# Sheet2.net
KiCad netlist of a schematic drawn in Altium Designer
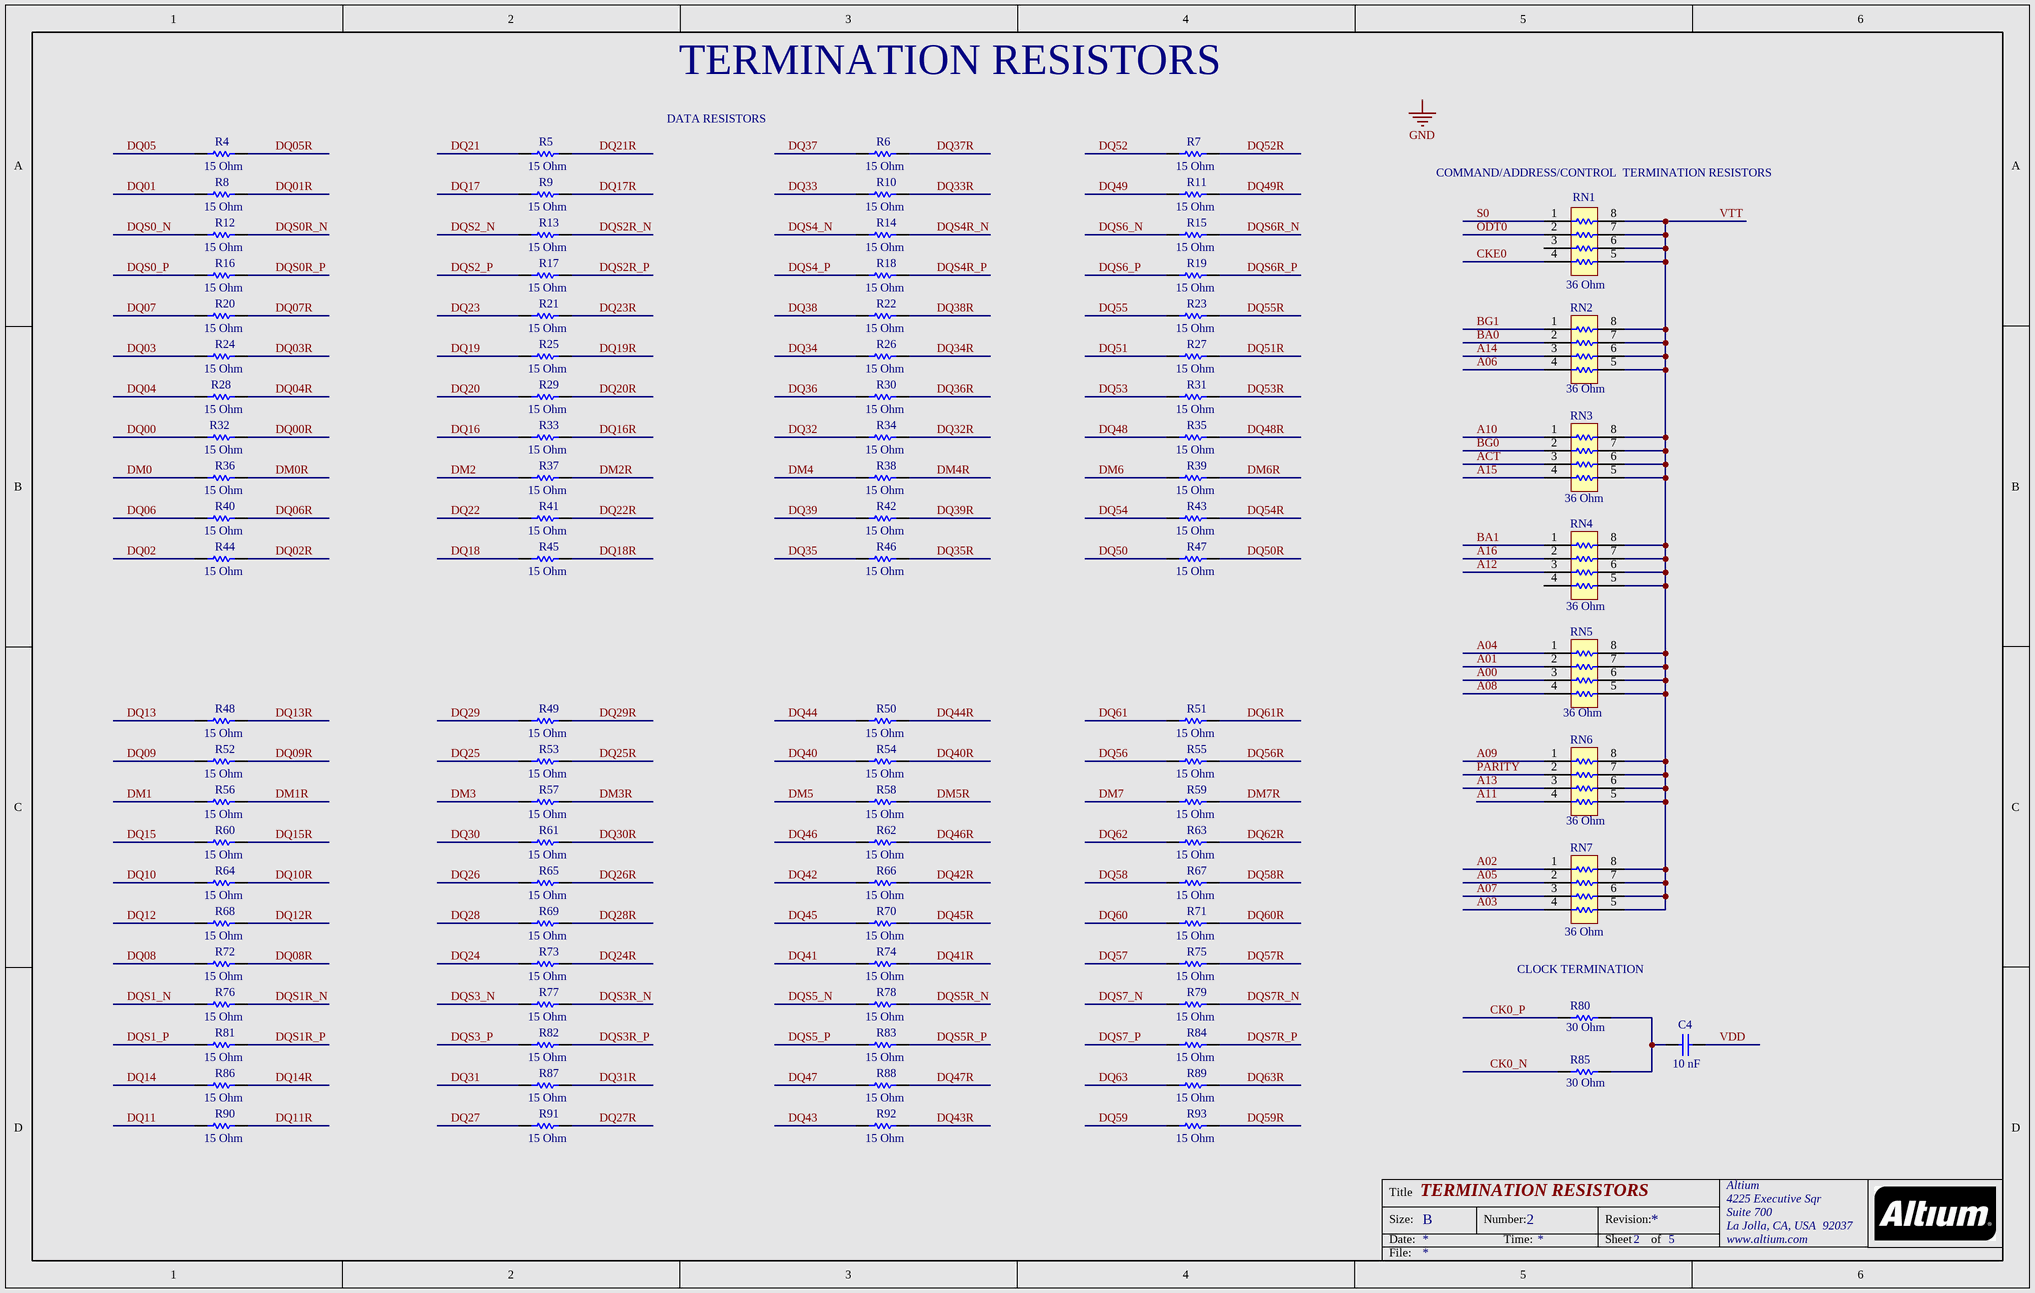
[diagram p0: Sheet2.SchDoc]

(export (version "E")
  (design (tool "Eeschema 10.0.6"))
  (components
    (comp (ref "C4")
      (value "C1005X7R1E103M050BB")
      (footprint "CAPC1005X55X10NL05")
      (description "Chip Capacitor, 10 nF, +/- 15%, 25 V, -55 to 125 degC, 0402 (1005 Metric), RoHS, Tape and Reel")
      (fields (field (name "TOLERANCE") "20%") (field (name "CAPACITANCE") "10 nF"))
      (libsource (lib "Altium Content Vault") (part "CMP-1663-00012-1"))
    )
    (comp (ref "R4")
      (value "ERJ-1GEJ150C")
      (footprint "RESC0603X26X15ML03T05")
      (description "Chip Resistor, 15 Ohm, +/- 5%, 0.05 W, -55 to 125 degC, 0201 (0603 Metric), RoHS, Tape and Reel")
      (fields (field (name "RESISTANCE") "15 Ohm") (field (name "TOLERANCE") "5%"))
      (libsource (lib "Altium Content Vault") (part "CMP-2004-03155-3"))
    )
    (comp (ref "R5")
      (value "ERJ-1GEJ150C")
      (footprint "RESC0603X26X15ML03T05")
      (description "Chip Resistor, 15 Ohm, +/- 5%, 0.05 W, -55 to 125 degC, 0201 (0603 Metric), RoHS, Tape and Reel")
      (fields (field (name "RESISTANCE") "15 Ohm") (field (name "TOLERANCE") "5%"))
      (libsource (lib "Altium Content Vault") (part "CMP-2004-03155-3"))
    )
    (comp (ref "R6")
      (value "ERJ-1GEJ150C")
      (footprint "RESC0603X26X15ML03T05")
      (description "Chip Resistor, 15 Ohm, +/- 5%, 0.05 W, -55 to 125 degC, 0201 (0603 Metric), RoHS, Tape and Reel")
      (fields (field (name "RESISTANCE") "15 Ohm") (field (name "TOLERANCE") "5%"))
      (libsource (lib "Altium Content Vault") (part "CMP-2004-03155-3"))
    )
    (comp (ref "R7")
      (value "ERJ-1GEJ150C")
      (footprint "RESC0603X26X15ML03T05")
      (description "Chip Resistor, 15 Ohm, +/- 5%, 0.05 W, -55 to 125 degC, 0201 (0603 Metric), RoHS, Tape and Reel")
      (fields (field (name "RESISTANCE") "15 Ohm") (field (name "TOLERANCE") "5%"))
      (libsource (lib "Altium Content Vault") (part "CMP-2004-03155-3"))
    )
    (comp (ref "R8")
      (value "ERJ-1GEJ150C")
      (footprint "RESC0603X26X15ML03T05")
      (description "Chip Resistor, 15 Ohm, +/- 5%, 0.05 W, -55 to 125 degC, 0201 (0603 Metric), RoHS, Tape and Reel")
      (fields (field (name "RESISTANCE") "15 Ohm") (field (name "TOLERANCE") "5%"))
      (libsource (lib "Altium Content Vault") (part "CMP-2004-03155-3"))
    )
    (comp (ref "R9")
      (value "ERJ-1GEJ150C")
      (footprint "RESC0603X26X15ML03T05")
      (description "Chip Resistor, 15 Ohm, +/- 5%, 0.05 W, -55 to 125 degC, 0201 (0603 Metric), RoHS, Tape and Reel")
      (fields (field (name "RESISTANCE") "15 Ohm") (field (name "TOLERANCE") "5%"))
      (libsource (lib "Altium Content Vault") (part "CMP-2004-03155-3"))
    )
    (comp (ref "R10")
      (value "ERJ-1GEJ150C")
      (footprint "RESC0603X26X15ML03T05")
      (description "Chip Resistor, 15 Ohm, +/- 5%, 0.05 W, -55 to 125 degC, 0201 (0603 Metric), RoHS, Tape and Reel")
      (fields (field (name "RESISTANCE") "15 Ohm") (field (name "TOLERANCE") "5%"))
      (libsource (lib "Altium Content Vault") (part "CMP-2004-03155-3"))
    )
    (comp (ref "R11")
      (value "ERJ-1GEJ150C")
      (footprint "RESC0603X26X15ML03T05")
      (description "Chip Resistor, 15 Ohm, +/- 5%, 0.05 W, -55 to 125 degC, 0201 (0603 Metric), RoHS, Tape and Reel")
      (fields (field (name "RESISTANCE") "15 Ohm") (field (name "TOLERANCE") "5%"))
      (libsource (lib "Altium Content Vault") (part "CMP-2004-03155-3"))
    )
    (comp (ref "R12")
      (value "ERJ-1GEJ150C")
      (footprint "RESC0603X26X15ML03T05")
      (description "Chip Resistor, 15 Ohm, +/- 5%, 0.05 W, -55 to 125 degC, 0201 (0603 Metric), RoHS, Tape and Reel")
      (fields (field (name "RESISTANCE") "15 Ohm") (field (name "TOLERANCE") "5%"))
      (libsource (lib "Altium Content Vault") (part "CMP-2004-03155-3"))
    )
    (comp (ref "R13")
      (value "ERJ-1GEJ150C")
      (footprint "RESC0603X26X15ML03T05")
      (description "Chip Resistor, 15 Ohm, +/- 5%, 0.05 W, -55 to 125 degC, 0201 (0603 Metric), RoHS, Tape and Reel")
      (fields (field (name "RESISTANCE") "15 Ohm") (field (name "TOLERANCE") "5%"))
      (libsource (lib "Altium Content Vault") (part "CMP-2004-03155-3"))
    )
    (comp (ref "R14")
      (value "ERJ-1GEJ150C")
      (footprint "RESC0603X26X15ML03T05")
      (description "Chip Resistor, 15 Ohm, +/- 5%, 0.05 W, -55 to 125 degC, 0201 (0603 Metric), RoHS, Tape and Reel")
      (fields (field (name "RESISTANCE") "15 Ohm") (field (name "TOLERANCE") "5%"))
      (libsource (lib "Altium Content Vault") (part "CMP-2004-03155-3"))
    )
    (comp (ref "R15")
      (value "ERJ-1GEJ150C")
      (footprint "RESC0603X26X15ML03T05")
      (description "Chip Resistor, 15 Ohm, +/- 5%, 0.05 W, -55 to 125 degC, 0201 (0603 Metric), RoHS, Tape and Reel")
      (fields (field (name "RESISTANCE") "15 Ohm") (field (name "TOLERANCE") "5%"))
      (libsource (lib "Altium Content Vault") (part "CMP-2004-03155-3"))
    )
    (comp (ref "R16")
      (value "ERJ-1GEJ150C")
      (footprint "RESC0603X26X15ML03T05")
      (description "Chip Resistor, 15 Ohm, +/- 5%, 0.05 W, -55 to 125 degC, 0201 (0603 Metric), RoHS, Tape and Reel")
      (fields (field (name "RESISTANCE") "15 Ohm") (field (name "TOLERANCE") "5%"))
      (libsource (lib "Altium Content Vault") (part "CMP-2004-03155-3"))
    )
    (comp (ref "R17")
      (value "ERJ-1GEJ150C")
      (footprint "RESC0603X26X15ML03T05")
      (description "Chip Resistor, 15 Ohm, +/- 5%, 0.05 W, -55 to 125 degC, 0201 (0603 Metric), RoHS, Tape and Reel")
      (fields (field (name "RESISTANCE") "15 Ohm") (field (name "TOLERANCE") "5%"))
      (libsource (lib "Altium Content Vault") (part "CMP-2004-03155-3"))
    )
    (comp (ref "R18")
      (value "ERJ-1GEJ150C")
      (footprint "RESC0603X26X15ML03T05")
      (description "Chip Resistor, 15 Ohm, +/- 5%, 0.05 W, -55 to 125 degC, 0201 (0603 Metric), RoHS, Tape and Reel")
      (fields (field (name "RESISTANCE") "15 Ohm") (field (name "TOLERANCE") "5%"))
      (libsource (lib "Altium Content Vault") (part "CMP-2004-03155-3"))
    )
    (comp (ref "R19")
      (value "ERJ-1GEJ150C")
      (footprint "RESC0603X26X15ML03T05")
      (description "Chip Resistor, 15 Ohm, +/- 5%, 0.05 W, -55 to 125 degC, 0201 (0603 Metric), RoHS, Tape and Reel")
      (fields (field (name "RESISTANCE") "15 Ohm") (field (name "TOLERANCE") "5%"))
      (libsource (lib "Altium Content Vault") (part "CMP-2004-03155-3"))
    )
    (comp (ref "R20")
      (value "ERJ-1GEJ150C")
      (footprint "RESC0603X26X15ML03T05")
      (description "Chip Resistor, 15 Ohm, +/- 5%, 0.05 W, -55 to 125 degC, 0201 (0603 Metric), RoHS, Tape and Reel")
      (fields (field (name "RESISTANCE") "15 Ohm") (field (name "TOLERANCE") "5%"))
      (libsource (lib "Altium Content Vault") (part "CMP-2004-03155-3"))
    )
    (comp (ref "R21")
      (value "ERJ-1GEJ150C")
      (footprint "RESC0603X26X15ML03T05")
      (description "Chip Resistor, 15 Ohm, +/- 5%, 0.05 W, -55 to 125 degC, 0201 (0603 Metric), RoHS, Tape and Reel")
      (fields (field (name "RESISTANCE") "15 Ohm") (field (name "TOLERANCE") "5%"))
      (libsource (lib "Altium Content Vault") (part "CMP-2004-03155-3"))
    )
    (comp (ref "R22")
      (value "ERJ-1GEJ150C")
      (footprint "RESC0603X26X15ML03T05")
      (description "Chip Resistor, 15 Ohm, +/- 5%, 0.05 W, -55 to 125 degC, 0201 (0603 Metric), RoHS, Tape and Reel")
      (fields (field (name "RESISTANCE") "15 Ohm") (field (name "TOLERANCE") "5%"))
      (libsource (lib "Altium Content Vault") (part "CMP-2004-03155-3"))
    )
    (comp (ref "R23")
      (value "ERJ-1GEJ150C")
      (footprint "RESC0603X26X15ML03T05")
      (description "Chip Resistor, 15 Ohm, +/- 5%, 0.05 W, -55 to 125 degC, 0201 (0603 Metric), RoHS, Tape and Reel")
      (fields (field (name "RESISTANCE") "15 Ohm") (field (name "TOLERANCE") "5%"))
      (libsource (lib "Altium Content Vault") (part "CMP-2004-03155-3"))
    )
    (comp (ref "R24")
      (value "ERJ-1GEJ150C")
      (footprint "RESC0603X26X15ML03T05")
      (description "Chip Resistor, 15 Ohm, +/- 5%, 0.05 W, -55 to 125 degC, 0201 (0603 Metric), RoHS, Tape and Reel")
      (fields (field (name "RESISTANCE") "15 Ohm") (field (name "TOLERANCE") "5%"))
      (libsource (lib "Altium Content Vault") (part "CMP-2004-03155-3"))
    )
    (comp (ref "R25")
      (value "ERJ-1GEJ150C")
      (footprint "RESC0603X26X15ML03T05")
      (description "Chip Resistor, 15 Ohm, +/- 5%, 0.05 W, -55 to 125 degC, 0201 (0603 Metric), RoHS, Tape and Reel")
      (fields (field (name "RESISTANCE") "15 Ohm") (field (name "TOLERANCE") "5%"))
      (libsource (lib "Altium Content Vault") (part "CMP-2004-03155-3"))
    )
    (comp (ref "R26")
      (value "ERJ-1GEJ150C")
      (footprint "RESC0603X26X15ML03T05")
      (description "Chip Resistor, 15 Ohm, +/- 5%, 0.05 W, -55 to 125 degC, 0201 (0603 Metric), RoHS, Tape and Reel")
      (fields (field (name "RESISTANCE") "15 Ohm") (field (name "TOLERANCE") "5%"))
      (libsource (lib "Altium Content Vault") (part "CMP-2004-03155-3"))
    )
    (comp (ref "R27")
      (value "ERJ-1GEJ150C")
      (footprint "RESC0603X26X15ML03T05")
      (description "Chip Resistor, 15 Ohm, +/- 5%, 0.05 W, -55 to 125 degC, 0201 (0603 Metric), RoHS, Tape and Reel")
      (fields (field (name "RESISTANCE") "15 Ohm") (field (name "TOLERANCE") "5%"))
      (libsource (lib "Altium Content Vault") (part "CMP-2004-03155-3"))
    )
    (comp (ref "R28")
      (value "ERJ-1GEJ150C")
      (footprint "RESC0603X26X15ML03T05")
      (description "Chip Resistor, 15 Ohm, +/- 5%, 0.05 W, -55 to 125 degC, 0201 (0603 Metric), RoHS, Tape and Reel")
      (fields (field (name "RESISTANCE") "15 Ohm") (field (name "TOLERANCE") "5%"))
      (libsource (lib "Altium Content Vault") (part "CMP-2004-03155-3"))
    )
    (comp (ref "R29")
      (value "ERJ-1GEJ150C")
      (footprint "RESC0603X26X15ML03T05")
      (description "Chip Resistor, 15 Ohm, +/- 5%, 0.05 W, -55 to 125 degC, 0201 (0603 Metric), RoHS, Tape and Reel")
      (fields (field (name "RESISTANCE") "15 Ohm") (field (name "TOLERANCE") "5%"))
      (libsource (lib "Altium Content Vault") (part "CMP-2004-03155-3"))
    )
    (comp (ref "R30")
      (value "ERJ-1GEJ150C")
      (footprint "RESC0603X26X15ML03T05")
      (description "Chip Resistor, 15 Ohm, +/- 5%, 0.05 W, -55 to 125 degC, 0201 (0603 Metric), RoHS, Tape and Reel")
      (fields (field (name "RESISTANCE") "15 Ohm") (field (name "TOLERANCE") "5%"))
      (libsource (lib "Altium Content Vault") (part "CMP-2004-03155-3"))
    )
    (comp (ref "R31")
      (value "ERJ-1GEJ150C")
      (footprint "RESC0603X26X15ML03T05")
      (description "Chip Resistor, 15 Ohm, +/- 5%, 0.05 W, -55 to 125 degC, 0201 (0603 Metric), RoHS, Tape and Reel")
      (fields (field (name "RESISTANCE") "15 Ohm") (field (name "TOLERANCE") "5%"))
      (libsource (lib "Altium Content Vault") (part "CMP-2004-03155-3"))
    )
    (comp (ref "R32")
      (value "ERJ-1GEJ150C")
      (footprint "RESC0603X26X15ML03T05")
      (description "Chip Resistor, 15 Ohm, +/- 5%, 0.05 W, -55 to 125 degC, 0201 (0603 Metric), RoHS, Tape and Reel")
      (fields (field (name "RESISTANCE") "15 Ohm") (field (name "TOLERANCE") "5%"))
      (libsource (lib "Altium Content Vault") (part "CMP-2004-03155-3"))
    )
    (comp (ref "R33")
      (value "ERJ-1GEJ150C")
      (footprint "RESC0603X26X15ML03T05")
      (description "Chip Resistor, 15 Ohm, +/- 5%, 0.05 W, -55 to 125 degC, 0201 (0603 Metric), RoHS, Tape and Reel")
      (fields (field (name "RESISTANCE") "15 Ohm") (field (name "TOLERANCE") "5%"))
      (libsource (lib "Altium Content Vault") (part "CMP-2004-03155-3"))
    )
    (comp (ref "R34")
      (value "ERJ-1GEJ150C")
      (footprint "RESC0603X26X15ML03T05")
      (description "Chip Resistor, 15 Ohm, +/- 5%, 0.05 W, -55 to 125 degC, 0201 (0603 Metric), RoHS, Tape and Reel")
      (fields (field (name "RESISTANCE") "15 Ohm") (field (name "TOLERANCE") "5%"))
      (libsource (lib "Altium Content Vault") (part "CMP-2004-03155-3"))
    )
    (comp (ref "R35")
      (value "ERJ-1GEJ150C")
      (footprint "RESC0603X26X15ML03T05")
      (description "Chip Resistor, 15 Ohm, +/- 5%, 0.05 W, -55 to 125 degC, 0201 (0603 Metric), RoHS, Tape and Reel")
      (fields (field (name "RESISTANCE") "15 Ohm") (field (name "TOLERANCE") "5%"))
      (libsource (lib "Altium Content Vault") (part "CMP-2004-03155-3"))
    )
    (comp (ref "R36")
      (value "ERJ-1GEJ150C")
      (footprint "RESC0603X26X15ML03T05")
      (description "Chip Resistor, 15 Ohm, +/- 5%, 0.05 W, -55 to 125 degC, 0201 (0603 Metric), RoHS, Tape and Reel")
      (fields (field (name "RESISTANCE") "15 Ohm") (field (name "TOLERANCE") "5%"))
      (libsource (lib "Altium Content Vault") (part "CMP-2004-03155-3"))
    )
    (comp (ref "R37")
      (value "ERJ-1GEJ150C")
      (footprint "RESC0603X26X15ML03T05")
      (description "Chip Resistor, 15 Ohm, +/- 5%, 0.05 W, -55 to 125 degC, 0201 (0603 Metric), RoHS, Tape and Reel")
      (fields (field (name "RESISTANCE") "15 Ohm") (field (name "TOLERANCE") "5%"))
      (libsource (lib "Altium Content Vault") (part "CMP-2004-03155-3"))
    )
    (comp (ref "R38")
      (value "ERJ-1GEJ150C")
      (footprint "RESC0603X26X15ML03T05")
      (description "Chip Resistor, 15 Ohm, +/- 5%, 0.05 W, -55 to 125 degC, 0201 (0603 Metric), RoHS, Tape and Reel")
      (fields (field (name "RESISTANCE") "15 Ohm") (field (name "TOLERANCE") "5%"))
      (libsource (lib "Altium Content Vault") (part "CMP-2004-03155-3"))
    )
    (comp (ref "R39")
      (value "ERJ-1GEJ150C")
      (footprint "RESC0603X26X15ML03T05")
      (description "Chip Resistor, 15 Ohm, +/- 5%, 0.05 W, -55 to 125 degC, 0201 (0603 Metric), RoHS, Tape and Reel")
      (fields (field (name "RESISTANCE") "15 Ohm") (field (name "TOLERANCE") "5%"))
      (libsource (lib "Altium Content Vault") (part "CMP-2004-03155-3"))
    )
    (comp (ref "R40")
      (value "ERJ-1GEJ150C")
      (footprint "RESC0603X26X15ML03T05")
      (description "Chip Resistor, 15 Ohm, +/- 5%, 0.05 W, -55 to 125 degC, 0201 (0603 Metric), RoHS, Tape and Reel")
      (fields (field (name "RESISTANCE") "15 Ohm") (field (name "TOLERANCE") "5%"))
      (libsource (lib "Altium Content Vault") (part "CMP-2004-03155-3"))
    )
    (comp (ref "R41")
      (value "ERJ-1GEJ150C")
      (footprint "RESC0603X26X15ML03T05")
      (description "Chip Resistor, 15 Ohm, +/- 5%, 0.05 W, -55 to 125 degC, 0201 (0603 Metric), RoHS, Tape and Reel")
      (fields (field (name "RESISTANCE") "15 Ohm") (field (name "TOLERANCE") "5%"))
      (libsource (lib "Altium Content Vault") (part "CMP-2004-03155-3"))
    )
    (comp (ref "R42")
      (value "ERJ-1GEJ150C")
      (footprint "RESC0603X26X15ML03T05")
      (description "Chip Resistor, 15 Ohm, +/- 5%, 0.05 W, -55 to 125 degC, 0201 (0603 Metric), RoHS, Tape and Reel")
      (fields (field (name "RESISTANCE") "15 Ohm") (field (name "TOLERANCE") "5%"))
      (libsource (lib "Altium Content Vault") (part "CMP-2004-03155-3"))
    )
    (comp (ref "R43")
      (value "ERJ-1GEJ150C")
      (footprint "RESC0603X26X15ML03T05")
      (description "Chip Resistor, 15 Ohm, +/- 5%, 0.05 W, -55 to 125 degC, 0201 (0603 Metric), RoHS, Tape and Reel")
      (fields (field (name "RESISTANCE") "15 Ohm") (field (name "TOLERANCE") "5%"))
      (libsource (lib "Altium Content Vault") (part "CMP-2004-03155-3"))
    )
    (comp (ref "R44")
      (value "ERJ-1GEJ150C")
      (footprint "RESC0603X26X15ML03T05")
      (description "Chip Resistor, 15 Ohm, +/- 5%, 0.05 W, -55 to 125 degC, 0201 (0603 Metric), RoHS, Tape and Reel")
      (fields (field (name "RESISTANCE") "15 Ohm") (field (name "TOLERANCE") "5%"))
      (libsource (lib "Altium Content Vault") (part "CMP-2004-03155-3"))
    )
    (comp (ref "R45")
      (value "ERJ-1GEJ150C")
      (footprint "RESC0603X26X15ML03T05")
      (description "Chip Resistor, 15 Ohm, +/- 5%, 0.05 W, -55 to 125 degC, 0201 (0603 Metric), RoHS, Tape and Reel")
      (fields (field (name "RESISTANCE") "15 Ohm") (field (name "TOLERANCE") "5%"))
      (libsource (lib "Altium Content Vault") (part "CMP-2004-03155-3"))
    )
    (comp (ref "R46")
      (value "ERJ-1GEJ150C")
      (footprint "RESC0603X26X15ML03T05")
      (description "Chip Resistor, 15 Ohm, +/- 5%, 0.05 W, -55 to 125 degC, 0201 (0603 Metric), RoHS, Tape and Reel")
      (fields (field (name "RESISTANCE") "15 Ohm") (field (name "TOLERANCE") "5%"))
      (libsource (lib "Altium Content Vault") (part "CMP-2004-03155-3"))
    )
    (comp (ref "R47")
      (value "ERJ-1GEJ150C")
      (footprint "RESC0603X26X15ML03T05")
      (description "Chip Resistor, 15 Ohm, +/- 5%, 0.05 W, -55 to 125 degC, 0201 (0603 Metric), RoHS, Tape and Reel")
      (fields (field (name "RESISTANCE") "15 Ohm") (field (name "TOLERANCE") "5%"))
      (libsource (lib "Altium Content Vault") (part "CMP-2004-03155-3"))
    )
    (comp (ref "R48")
      (value "ERJ-1GEJ150C")
      (footprint "RESC0603X26X15ML03T05")
      (description "Chip Resistor, 15 Ohm, +/- 5%, 0.05 W, -55 to 125 degC, 0201 (0603 Metric), RoHS, Tape and Reel")
      (fields (field (name "RESISTANCE") "15 Ohm") (field (name "TOLERANCE") "5%"))
      (libsource (lib "Altium Content Vault") (part "CMP-2004-03155-3"))
    )
    (comp (ref "R49")
      (value "ERJ-1GEJ150C")
      (footprint "RESC0603X26X15ML03T05")
      (description "Chip Resistor, 15 Ohm, +/- 5%, 0.05 W, -55 to 125 degC, 0201 (0603 Metric), RoHS, Tape and Reel")
      (fields (field (name "RESISTANCE") "15 Ohm") (field (name "TOLERANCE") "5%"))
      (libsource (lib "Altium Content Vault") (part "CMP-2004-03155-3"))
    )
    (comp (ref "R50")
      (value "ERJ-1GEJ150C")
      (footprint "RESC0603X26X15ML03T05")
      (description "Chip Resistor, 15 Ohm, +/- 5%, 0.05 W, -55 to 125 degC, 0201 (0603 Metric), RoHS, Tape and Reel")
      (fields (field (name "RESISTANCE") "15 Ohm") (field (name "TOLERANCE") "5%"))
      (libsource (lib "Altium Content Vault") (part "CMP-2004-03155-3"))
    )
    (comp (ref "R51")
      (value "ERJ-1GEJ150C")
      (footprint "RESC0603X26X15ML03T05")
      (description "Chip Resistor, 15 Ohm, +/- 5%, 0.05 W, -55 to 125 degC, 0201 (0603 Metric), RoHS, Tape and Reel")
      (fields (field (name "RESISTANCE") "15 Ohm") (field (name "TOLERANCE") "5%"))
      (libsource (lib "Altium Content Vault") (part "CMP-2004-03155-3"))
    )
    (comp (ref "R52")
      (value "ERJ-1GEJ150C")
      (footprint "RESC0603X26X15ML03T05")
      (description "Chip Resistor, 15 Ohm, +/- 5%, 0.05 W, -55 to 125 degC, 0201 (0603 Metric), RoHS, Tape and Reel")
      (fields (field (name "RESISTANCE") "15 Ohm") (field (name "TOLERANCE") "5%"))
      (libsource (lib "Altium Content Vault") (part "CMP-2004-03155-3"))
    )
    (comp (ref "R53")
      (value "ERJ-1GEJ150C")
      (footprint "RESC0603X26X15ML03T05")
      (description "Chip Resistor, 15 Ohm, +/- 5%, 0.05 W, -55 to 125 degC, 0201 (0603 Metric), RoHS, Tape and Reel")
      (fields (field (name "RESISTANCE") "15 Ohm") (field (name "TOLERANCE") "5%"))
      (libsource (lib "Altium Content Vault") (part "CMP-2004-03155-3"))
    )
    (comp (ref "R54")
      (value "ERJ-1GEJ150C")
      (footprint "RESC0603X26X15ML03T05")
      (description "Chip Resistor, 15 Ohm, +/- 5%, 0.05 W, -55 to 125 degC, 0201 (0603 Metric), RoHS, Tape and Reel")
      (fields (field (name "RESISTANCE") "15 Ohm") (field (name "TOLERANCE") "5%"))
      (libsource (lib "Altium Content Vault") (part "CMP-2004-03155-3"))
    )
    (comp (ref "R55")
      (value "ERJ-1GEJ150C")
      (footprint "RESC0603X26X15ML03T05")
      (description "Chip Resistor, 15 Ohm, +/- 5%, 0.05 W, -55 to 125 degC, 0201 (0603 Metric), RoHS, Tape and Reel")
      (fields (field (name "RESISTANCE") "15 Ohm") (field (name "TOLERANCE") "5%"))
      (libsource (lib "Altium Content Vault") (part "CMP-2004-03155-3"))
    )
    (comp (ref "R56")
      (value "ERJ-1GEJ150C")
      (footprint "RESC0603X26X15ML03T05")
      (description "Chip Resistor, 15 Ohm, +/- 5%, 0.05 W, -55 to 125 degC, 0201 (0603 Metric), RoHS, Tape and Reel")
      (fields (field (name "RESISTANCE") "15 Ohm") (field (name "TOLERANCE") "5%"))
      (libsource (lib "Altium Content Vault") (part "CMP-2004-03155-3"))
    )
    (comp (ref "R57")
      (value "ERJ-1GEJ150C")
      (footprint "RESC0603X26X15ML03T05")
      (description "Chip Resistor, 15 Ohm, +/- 5%, 0.05 W, -55 to 125 degC, 0201 (0603 Metric), RoHS, Tape and Reel")
      (fields (field (name "RESISTANCE") "15 Ohm") (field (name "TOLERANCE") "5%"))
      (libsource (lib "Altium Content Vault") (part "CMP-2004-03155-3"))
    )
    (comp (ref "R58")
      (value "ERJ-1GEJ150C")
      (footprint "RESC0603X26X15ML03T05")
      (description "Chip Resistor, 15 Ohm, +/- 5%, 0.05 W, -55 to 125 degC, 0201 (0603 Metric), RoHS, Tape and Reel")
      (fields (field (name "RESISTANCE") "15 Ohm") (field (name "TOLERANCE") "5%"))
      (libsource (lib "Altium Content Vault") (part "CMP-2004-03155-3"))
    )
    (comp (ref "R59")
      (value "ERJ-1GEJ150C")
      (footprint "RESC0603X26X15ML03T05")
      (description "Chip Resistor, 15 Ohm, +/- 5%, 0.05 W, -55 to 125 degC, 0201 (0603 Metric), RoHS, Tape and Reel")
      (fields (field (name "RESISTANCE") "15 Ohm") (field (name "TOLERANCE") "5%"))
      (libsource (lib "Altium Content Vault") (part "CMP-2004-03155-3"))
    )
    (comp (ref "R60")
      (value "ERJ-1GEJ150C")
      (footprint "RESC0603X26X15ML03T05")
      (description "Chip Resistor, 15 Ohm, +/- 5%, 0.05 W, -55 to 125 degC, 0201 (0603 Metric), RoHS, Tape and Reel")
      (fields (field (name "RESISTANCE") "15 Ohm") (field (name "TOLERANCE") "5%"))
      (libsource (lib "Altium Content Vault") (part "CMP-2004-03155-3"))
    )
    (comp (ref "R61")
      (value "ERJ-1GEJ150C")
      (footprint "RESC0603X26X15ML03T05")
      (description "Chip Resistor, 15 Ohm, +/- 5%, 0.05 W, -55 to 125 degC, 0201 (0603 Metric), RoHS, Tape and Reel")
      (fields (field (name "RESISTANCE") "15 Ohm") (field (name "TOLERANCE") "5%"))
      (libsource (lib "Altium Content Vault") (part "CMP-2004-03155-3"))
    )
    (comp (ref "R62")
      (value "ERJ-1GEJ150C")
      (footprint "RESC0603X26X15ML03T05")
      (description "Chip Resistor, 15 Ohm, +/- 5%, 0.05 W, -55 to 125 degC, 0201 (0603 Metric), RoHS, Tape and Reel")
      (fields (field (name "RESISTANCE") "15 Ohm") (field (name "TOLERANCE") "5%"))
      (libsource (lib "Altium Content Vault") (part "CMP-2004-03155-3"))
    )
    (comp (ref "R63")
      (value "ERJ-1GEJ150C")
      (footprint "RESC0603X26X15ML03T05")
      (description "Chip Resistor, 15 Ohm, +/- 5%, 0.05 W, -55 to 125 degC, 0201 (0603 Metric), RoHS, Tape and Reel")
      (fields (field (name "RESISTANCE") "15 Ohm") (field (name "TOLERANCE") "5%"))
      (libsource (lib "Altium Content Vault") (part "CMP-2004-03155-3"))
    )
    (comp (ref "R64")
      (value "ERJ-1GEJ150C")
      (footprint "RESC0603X26X15ML03T05")
      (description "Chip Resistor, 15 Ohm, +/- 5%, 0.05 W, -55 to 125 degC, 0201 (0603 Metric), RoHS, Tape and Reel")
      (fields (field (name "RESISTANCE") "15 Ohm") (field (name "TOLERANCE") "5%"))
      (libsource (lib "Altium Content Vault") (part "CMP-2004-03155-3"))
    )
    (comp (ref "R65")
      (value "ERJ-1GEJ150C")
      (footprint "RESC0603X26X15ML03T05")
      (description "Chip Resistor, 15 Ohm, +/- 5%, 0.05 W, -55 to 125 degC, 0201 (0603 Metric), RoHS, Tape and Reel")
      (fields (field (name "RESISTANCE") "15 Ohm") (field (name "TOLERANCE") "5%"))
      (libsource (lib "Altium Content Vault") (part "CMP-2004-03155-3"))
    )
    (comp (ref "R66")
      (value "ERJ-1GEJ150C")
      (footprint "RESC0603X26X15ML03T05")
      (description "Chip Resistor, 15 Ohm, +/- 5%, 0.05 W, -55 to 125 degC, 0201 (0603 Metric), RoHS, Tape and Reel")
      (fields (field (name "RESISTANCE") "15 Ohm") (field (name "TOLERANCE") "5%"))
      (libsource (lib "Altium Content Vault") (part "CMP-2004-03155-3"))
    )
    (comp (ref "R67")
      (value "ERJ-1GEJ150C")
      (footprint "RESC0603X26X15ML03T05")
      (description "Chip Resistor, 15 Ohm, +/- 5%, 0.05 W, -55 to 125 degC, 0201 (0603 Metric), RoHS, Tape and Reel")
      (fields (field (name "RESISTANCE") "15 Ohm") (field (name "TOLERANCE") "5%"))
      (libsource (lib "Altium Content Vault") (part "CMP-2004-03155-3"))
    )
    (comp (ref "R68")
      (value "ERJ-1GEJ150C")
      (footprint "RESC0603X26X15ML03T05")
      (description "Chip Resistor, 15 Ohm, +/- 5%, 0.05 W, -55 to 125 degC, 0201 (0603 Metric), RoHS, Tape and Reel")
      (fields (field (name "RESISTANCE") "15 Ohm") (field (name "TOLERANCE") "5%"))
      (libsource (lib "Altium Content Vault") (part "CMP-2004-03155-3"))
    )
    (comp (ref "R69")
      (value "ERJ-1GEJ150C")
      (footprint "RESC0603X26X15ML03T05")
      (description "Chip Resistor, 15 Ohm, +/- 5%, 0.05 W, -55 to 125 degC, 0201 (0603 Metric), RoHS, Tape and Reel")
      (fields (field (name "RESISTANCE") "15 Ohm") (field (name "TOLERANCE") "5%"))
      (libsource (lib "Altium Content Vault") (part "CMP-2004-03155-3"))
    )
    (comp (ref "R70")
      (value "ERJ-1GEJ150C")
      (footprint "RESC0603X26X15ML03T05")
      (description "Chip Resistor, 15 Ohm, +/- 5%, 0.05 W, -55 to 125 degC, 0201 (0603 Metric), RoHS, Tape and Reel")
      (fields (field (name "RESISTANCE") "15 Ohm") (field (name "TOLERANCE") "5%"))
      (libsource (lib "Altium Content Vault") (part "CMP-2004-03155-3"))
    )
    (comp (ref "R71")
      (value "ERJ-1GEJ150C")
      (footprint "RESC0603X26X15ML03T05")
      (description "Chip Resistor, 15 Ohm, +/- 5%, 0.05 W, -55 to 125 degC, 0201 (0603 Metric), RoHS, Tape and Reel")
      (fields (field (name "RESISTANCE") "15 Ohm") (field (name "TOLERANCE") "5%"))
      (libsource (lib "Altium Content Vault") (part "CMP-2004-03155-3"))
    )
    (comp (ref "R72")
      (value "ERJ-1GEJ150C")
      (footprint "RESC0603X26X15ML03T05")
      (description "Chip Resistor, 15 Ohm, +/- 5%, 0.05 W, -55 to 125 degC, 0201 (0603 Metric), RoHS, Tape and Reel")
      (fields (field (name "RESISTANCE") "15 Ohm") (field (name "TOLERANCE") "5%"))
      (libsource (lib "Altium Content Vault") (part "CMP-2004-03155-3"))
    )
    (comp (ref "R73")
      (value "ERJ-1GEJ150C")
      (footprint "RESC0603X26X15ML03T05")
      (description "Chip Resistor, 15 Ohm, +/- 5%, 0.05 W, -55 to 125 degC, 0201 (0603 Metric), RoHS, Tape and Reel")
      (fields (field (name "RESISTANCE") "15 Ohm") (field (name "TOLERANCE") "5%"))
      (libsource (lib "Altium Content Vault") (part "CMP-2004-03155-3"))
    )
    (comp (ref "R74")
      (value "ERJ-1GEJ150C")
      (footprint "RESC0603X26X15ML03T05")
      (description "Chip Resistor, 15 Ohm, +/- 5%, 0.05 W, -55 to 125 degC, 0201 (0603 Metric), RoHS, Tape and Reel")
      (fields (field (name "RESISTANCE") "15 Ohm") (field (name "TOLERANCE") "5%"))
      (libsource (lib "Altium Content Vault") (part "CMP-2004-03155-3"))
    )
    (comp (ref "R75")
      (value "ERJ-1GEJ150C")
      (footprint "RESC0603X26X15ML03T05")
      (description "Chip Resistor, 15 Ohm, +/- 5%, 0.05 W, -55 to 125 degC, 0201 (0603 Metric), RoHS, Tape and Reel")
      (fields (field (name "RESISTANCE") "15 Ohm") (field (name "TOLERANCE") "5%"))
      (libsource (lib "Altium Content Vault") (part "CMP-2004-03155-3"))
    )
    (comp (ref "R76")
      (value "ERJ-1GEJ150C")
      (footprint "RESC0603X26X15ML03T05")
      (description "Chip Resistor, 15 Ohm, +/- 5%, 0.05 W, -55 to 125 degC, 0201 (0603 Metric), RoHS, Tape and Reel")
      (fields (field (name "RESISTANCE") "15 Ohm") (field (name "TOLERANCE") "5%"))
      (libsource (lib "Altium Content Vault") (part "CMP-2004-03155-3"))
    )
    (comp (ref "R77")
      (value "ERJ-1GEJ150C")
      (footprint "RESC0603X26X15ML03T05")
      (description "Chip Resistor, 15 Ohm, +/- 5%, 0.05 W, -55 to 125 degC, 0201 (0603 Metric), RoHS, Tape and Reel")
      (fields (field (name "RESISTANCE") "15 Ohm") (field (name "TOLERANCE") "5%"))
      (libsource (lib "Altium Content Vault") (part "CMP-2004-03155-3"))
    )
    (comp (ref "R78")
      (value "ERJ-1GEJ150C")
      (footprint "RESC0603X26X15ML03T05")
      (description "Chip Resistor, 15 Ohm, +/- 5%, 0.05 W, -55 to 125 degC, 0201 (0603 Metric), RoHS, Tape and Reel")
      (fields (field (name "RESISTANCE") "15 Ohm") (field (name "TOLERANCE") "5%"))
      (libsource (lib "Altium Content Vault") (part "CMP-2004-03155-3"))
    )
    (comp (ref "R79")
      (value "ERJ-1GEJ150C")
      (footprint "RESC0603X26X15ML03T05")
      (description "Chip Resistor, 15 Ohm, +/- 5%, 0.05 W, -55 to 125 degC, 0201 (0603 Metric), RoHS, Tape and Reel")
      (fields (field (name "RESISTANCE") "15 Ohm") (field (name "TOLERANCE") "5%"))
      (libsource (lib "Altium Content Vault") (part "CMP-2004-03155-3"))
    )
    (comp (ref "R80")
      (value "RC0402JR-0730RL")
      (footprint "RESC1005X40X25NL5T10")
      (description "Chip Resistor, 30 Ohm, +/- 5%, 0.063 W, -55 to 155 degC, 0402 (1005 Metric), RoHS, Tape and Reel")
      (fields (field (name "RESISTANCE") "30 Ohm") (field (name "TOLERANCE") "5%"))
      (libsource (lib "Altium Content Vault") (part "CMP-2002-07983-2"))
    )
    (comp (ref "R81")
      (value "ERJ-1GEJ150C")
      (footprint "RESC0603X26X15ML03T05")
      (description "Chip Resistor, 15 Ohm, +/- 5%, 0.05 W, -55 to 125 degC, 0201 (0603 Metric), RoHS, Tape and Reel")
      (fields (field (name "RESISTANCE") "15 Ohm") (field (name "TOLERANCE") "5%"))
      (libsource (lib "Altium Content Vault") (part "CMP-2004-03155-3"))
    )
    (comp (ref "R82")
      (value "ERJ-1GEJ150C")
      (footprint "RESC0603X26X15ML03T05")
      (description "Chip Resistor, 15 Ohm, +/- 5%, 0.05 W, -55 to 125 degC, 0201 (0603 Metric), RoHS, Tape and Reel")
      (fields (field (name "RESISTANCE") "15 Ohm") (field (name "TOLERANCE") "5%"))
      (libsource (lib "Altium Content Vault") (part "CMP-2004-03155-3"))
    )
    (comp (ref "R83")
      (value "ERJ-1GEJ150C")
      (footprint "RESC0603X26X15ML03T05")
      (description "Chip Resistor, 15 Ohm, +/- 5%, 0.05 W, -55 to 125 degC, 0201 (0603 Metric), RoHS, Tape and Reel")
      (fields (field (name "RESISTANCE") "15 Ohm") (field (name "TOLERANCE") "5%"))
      (libsource (lib "Altium Content Vault") (part "CMP-2004-03155-3"))
    )
    (comp (ref "R84")
      (value "ERJ-1GEJ150C")
      (footprint "RESC0603X26X15ML03T05")
      (description "Chip Resistor, 15 Ohm, +/- 5%, 0.05 W, -55 to 125 degC, 0201 (0603 Metric), RoHS, Tape and Reel")
      (fields (field (name "RESISTANCE") "15 Ohm") (field (name "TOLERANCE") "5%"))
      (libsource (lib "Altium Content Vault") (part "CMP-2004-03155-3"))
    )
    (comp (ref "R85")
      (value "RC0402JR-0730RL")
      (footprint "RESC1005X40X25NL5T10")
      (description "Chip Resistor, 30 Ohm, +/- 5%, 0.063 W, -55 to 155 degC, 0402 (1005 Metric), RoHS, Tape and Reel")
      (fields (field (name "RESISTANCE") "30 Ohm") (field (name "TOLERANCE") "5%"))
      (libsource (lib "Altium Content Vault") (part "CMP-2002-07983-2"))
    )
    (comp (ref "R86")
      (value "ERJ-1GEJ150C")
      (footprint "RESC0603X26X15ML03T05")
      (description "Chip Resistor, 15 Ohm, +/- 5%, 0.05 W, -55 to 125 degC, 0201 (0603 Metric), RoHS, Tape and Reel")
      (fields (field (name "RESISTANCE") "15 Ohm") (field (name "TOLERANCE") "5%"))
      (libsource (lib "Altium Content Vault") (part "CMP-2004-03155-3"))
    )
    (comp (ref "R87")
      (value "ERJ-1GEJ150C")
      (footprint "RESC0603X26X15ML03T05")
      (description "Chip Resistor, 15 Ohm, +/- 5%, 0.05 W, -55 to 125 degC, 0201 (0603 Metric), RoHS, Tape and Reel")
      (fields (field (name "RESISTANCE") "15 Ohm") (field (name "TOLERANCE") "5%"))
      (libsource (lib "Altium Content Vault") (part "CMP-2004-03155-3"))
    )
    (comp (ref "R88")
      (value "ERJ-1GEJ150C")
      (footprint "RESC0603X26X15ML03T05")
      (description "Chip Resistor, 15 Ohm, +/- 5%, 0.05 W, -55 to 125 degC, 0201 (0603 Metric), RoHS, Tape and Reel")
      (fields (field (name "RESISTANCE") "15 Ohm") (field (name "TOLERANCE") "5%"))
      (libsource (lib "Altium Content Vault") (part "CMP-2004-03155-3"))
    )
    (comp (ref "R89")
      (value "ERJ-1GEJ150C")
      (footprint "RESC0603X26X15ML03T05")
      (description "Chip Resistor, 15 Ohm, +/- 5%, 0.05 W, -55 to 125 degC, 0201 (0603 Metric), RoHS, Tape and Reel")
      (fields (field (name "RESISTANCE") "15 Ohm") (field (name "TOLERANCE") "5%"))
      (libsource (lib "Altium Content Vault") (part "CMP-2004-03155-3"))
    )
    (comp (ref "R90")
      (value "ERJ-1GEJ150C")
      (footprint "RESC0603X26X15ML03T05")
      (description "Chip Resistor, 15 Ohm, +/- 5%, 0.05 W, -55 to 125 degC, 0201 (0603 Metric), RoHS, Tape and Reel")
      (fields (field (name "RESISTANCE") "15 Ohm") (field (name "TOLERANCE") "5%"))
      (libsource (lib "Altium Content Vault") (part "CMP-2004-03155-3"))
    )
    (comp (ref "R91")
      (value "ERJ-1GEJ150C")
      (footprint "RESC0603X26X15ML03T05")
      (description "Chip Resistor, 15 Ohm, +/- 5%, 0.05 W, -55 to 125 degC, 0201 (0603 Metric), RoHS, Tape and Reel")
      (fields (field (name "RESISTANCE") "15 Ohm") (field (name "TOLERANCE") "5%"))
      (libsource (lib "Altium Content Vault") (part "CMP-2004-03155-3"))
    )
    (comp (ref "R92")
      (value "ERJ-1GEJ150C")
      (footprint "RESC0603X26X15ML03T05")
      (description "Chip Resistor, 15 Ohm, +/- 5%, 0.05 W, -55 to 125 degC, 0201 (0603 Metric), RoHS, Tape and Reel")
      (fields (field (name "RESISTANCE") "15 Ohm") (field (name "TOLERANCE") "5%"))
      (libsource (lib "Altium Content Vault") (part "CMP-2004-03155-3"))
    )
    (comp (ref "R93")
      (value "ERJ-1GEJ150C")
      (footprint "RESC0603X26X15ML03T05")
      (description "Chip Resistor, 15 Ohm, +/- 5%, 0.05 W, -55 to 125 degC, 0201 (0603 Metric), RoHS, Tape and Reel")
      (fields (field (name "RESISTANCE") "15 Ohm") (field (name "TOLERANCE") "5%"))
      (libsource (lib "Altium Content Vault") (part "CMP-2004-03155-3"))
    )
    (comp (ref "RN1")
      (value "CAY10-360J4LF")
      (footprint "BOUR-CAY10-J4_V")
      (description "Chip Resistor Array, 36 Ohm, +/- 5%, 62.5 mW, -55 to 125 degC, 8-Pin SMD, RoHS, Tape and Reel")
      (fields (field (name "RESISTANCE") "36 Ohm") (field (name "TOLERANCE") "5%"))
      (libsource (lib "Altium Content Vault") (part "CMP-1734-00001-1"))
    )
    (comp (ref "RN2")
      (value "CAY10-360J4LF")
      (footprint "BOUR-CAY10-J4_V")
      (description "Chip Resistor Array, 36 Ohm, +/- 5%, 62.5 mW, -55 to 125 degC, 8-Pin SMD, RoHS, Tape and Reel")
      (fields (field (name "RESISTANCE") "36 Ohm") (field (name "TOLERANCE") "5%"))
      (libsource (lib "Altium Content Vault") (part "CMP-1734-00001-1"))
    )
    (comp (ref "RN3")
      (value "CAY10-360J4LF")
      (footprint "BOUR-CAY10-J4_V")
      (description "Chip Resistor Array, 36 Ohm, +/- 5%, 62.5 mW, -55 to 125 degC, 8-Pin SMD, RoHS, Tape and Reel")
      (fields (field (name "RESISTANCE") "36 Ohm") (field (name "TOLERANCE") "5%"))
      (libsource (lib "Altium Content Vault") (part "CMP-1734-00001-1"))
    )
    (comp (ref "RN4")
      (value "CAY10-360J4LF")
      (footprint "BOUR-CAY10-J4_V")
      (description "Chip Resistor Array, 36 Ohm, +/- 5%, 62.5 mW, -55 to 125 degC, 8-Pin SMD, RoHS, Tape and Reel")
      (fields (field (name "RESISTANCE") "36 Ohm") (field (name "TOLERANCE") "5%"))
      (libsource (lib "Altium Content Vault") (part "CMP-1734-00001-1"))
    )
    (comp (ref "RN5")
      (value "CAY10-360J4LF")
      (footprint "BOUR-CAY10-J4_V")
      (description "Chip Resistor Array, 36 Ohm, +/- 5%, 62.5 mW, -55 to 125 degC, 8-Pin SMD, RoHS, Tape and Reel")
      (fields (field (name "RESISTANCE") "36 Ohm") (field (name "TOLERANCE") "5%"))
      (libsource (lib "Altium Content Vault") (part "CMP-1734-00001-1"))
    )
    (comp (ref "RN6")
      (value "CAY10-360J4LF")
      (footprint "BOUR-CAY10-J4_V")
      (description "Chip Resistor Array, 36 Ohm, +/- 5%, 62.5 mW, -55 to 125 degC, 8-Pin SMD, RoHS, Tape and Reel")
      (fields (field (name "RESISTANCE") "36 Ohm") (field (name "TOLERANCE") "5%"))
      (libsource (lib "Altium Content Vault") (part "CMP-1734-00001-1"))
    )
    (comp (ref "RN7")
      (value "CAY10-360J4LF")
      (footprint "BOUR-CAY10-J4_V")
      (description "Chip Resistor Array, 36 Ohm, +/- 5%, 62.5 mW, -55 to 125 degC, 8-Pin SMD, RoHS, Tape and Reel")
      (fields (field (name "RESISTANCE") "36 Ohm") (field (name "TOLERANCE") "5%"))
      (libsource (lib "Altium Content Vault") (part "CMP-1734-00001-1"))
    )
  )
  (nets
    (net (code "1") (name "/A00") (class "Default")
      (node (ref "RN5") (pin "3") (pinfunction "3_3") (pintype "passive"))
    )
    (net (code "2") (name "/A01") (class "Default")
      (node (ref "RN5") (pin "2") (pinfunction "2_2") (pintype "passive"))
    )
    (net (code "3") (name "/A02") (class "Default")
      (node (ref "RN7") (pin "1") (pinfunction "1_1") (pintype "passive"))
    )
    (net (code "4") (name "/A03") (class "Default")
      (node (ref "RN7") (pin "4") (pinfunction "4_4") (pintype "passive"))
    )
    (net (code "5") (name "/A04") (class "Default")
      (node (ref "RN5") (pin "1") (pinfunction "1_1") (pintype "passive"))
    )
    (net (code "6") (name "/A05") (class "Default")
      (node (ref "RN7") (pin "2") (pinfunction "2_2") (pintype "passive"))
    )
    (net (code "7") (name "/A06") (class "Default")
      (node (ref "RN2") (pin "4") (pinfunction "4_4") (pintype "passive"))
    )
    (net (code "8") (name "/A07") (class "Default")
      (node (ref "RN7") (pin "3") (pinfunction "3_3") (pintype "passive"))
    )
    (net (code "9") (name "/A08") (class "Default")
      (node (ref "RN5") (pin "4") (pinfunction "4_4") (pintype "passive"))
    )
    (net (code "10") (name "/A09") (class "Default")
      (node (ref "RN6") (pin "1") (pinfunction "1_1") (pintype "passive"))
    )
    (net (code "11") (name "/A10") (class "Default")
      (node (ref "RN3") (pin "1") (pinfunction "1_1") (pintype "passive"))
    )
    (net (code "12") (name "/A11") (class "Default")
      (node (ref "RN6") (pin "4") (pinfunction "4_4") (pintype "passive"))
    )
    (net (code "13") (name "/A12") (class "Default")
      (node (ref "RN4") (pin "3") (pinfunction "3_3") (pintype "passive"))
    )
    (net (code "14") (name "/A13") (class "Default")
      (node (ref "RN6") (pin "3") (pinfunction "3_3") (pintype "passive"))
    )
    (net (code "15") (name "/A14") (class "Default")
      (node (ref "RN2") (pin "3") (pinfunction "3_3") (pintype "passive"))
    )
    (net (code "16") (name "/A15") (class "Default")
      (node (ref "RN3") (pin "4") (pinfunction "4_4") (pintype "passive"))
    )
    (net (code "17") (name "/A16") (class "Default")
      (node (ref "RN4") (pin "2") (pinfunction "2_2") (pintype "passive"))
    )
    (net (code "18") (name "/ACT") (class "Default")
      (node (ref "RN3") (pin "3") (pinfunction "3_3") (pintype "passive"))
    )
    (net (code "19") (name "/BA0") (class "Default")
      (node (ref "RN2") (pin "2") (pinfunction "2_2") (pintype "passive"))
    )
    (net (code "20") (name "/BA1") (class "Default")
      (node (ref "RN4") (pin "1") (pinfunction "1_1") (pintype "passive"))
    )
    (net (code "21") (name "/BG0") (class "Default")
      (node (ref "RN3") (pin "2") (pinfunction "2_2") (pintype "passive"))
    )
    (net (code "22") (name "/BG1") (class "Default")
      (node (ref "RN2") (pin "1") (pinfunction "1_1") (pintype "passive"))
    )
    (net (code "23") (name "/CK0_N") (class "Default")
      (node (ref "R85") (pin "1") (pinfunction "1_1") (pintype "passive"))
    )
    (net (code "24") (name "/CK0_P") (class "Default")
      (node (ref "R80") (pin "1") (pinfunction "1_1") (pintype "passive"))
    )
    (net (code "25") (name "/CKE0") (class "Default")
      (node (ref "RN1") (pin "4") (pinfunction "4_4") (pintype "passive"))
    )
    (net (code "26") (name "/DM0") (class "Default")
      (node (ref "R36") (pin "1") (pinfunction "1_1") (pintype "passive"))
    )
    (net (code "27") (name "/DM0R") (class "Default")
      (node (ref "R36") (pin "2") (pinfunction "2_2") (pintype "passive"))
    )
    (net (code "28") (name "/DM1") (class "Default")
      (node (ref "R56") (pin "1") (pinfunction "1_1") (pintype "passive"))
    )
    (net (code "29") (name "/DM1R") (class "Default")
      (node (ref "R56") (pin "2") (pinfunction "2_2") (pintype "passive"))
    )
    (net (code "30") (name "/DM2") (class "Default")
      (node (ref "R37") (pin "1") (pinfunction "1_1") (pintype "passive"))
    )
    (net (code "31") (name "/DM2R") (class "Default")
      (node (ref "R37") (pin "2") (pinfunction "2_2") (pintype "passive"))
    )
    (net (code "32") (name "/DM3") (class "Default")
      (node (ref "R57") (pin "1") (pinfunction "1_1") (pintype "passive"))
    )
    (net (code "33") (name "/DM3R") (class "Default")
      (node (ref "R57") (pin "2") (pinfunction "2_2") (pintype "passive"))
    )
    (net (code "34") (name "/DM4") (class "Default")
      (node (ref "R38") (pin "1") (pinfunction "1_1") (pintype "passive"))
    )
    (net (code "35") (name "/DM4R") (class "Default")
      (node (ref "R38") (pin "2") (pinfunction "2_2") (pintype "passive"))
    )
    (net (code "36") (name "/DM5") (class "Default")
      (node (ref "R58") (pin "1") (pinfunction "1_1") (pintype "passive"))
    )
    (net (code "37") (name "/DM5R") (class "Default")
      (node (ref "R58") (pin "2") (pinfunction "2_2") (pintype "passive"))
    )
    (net (code "38") (name "/DM6") (class "Default")
      (node (ref "R39") (pin "1") (pinfunction "1_1") (pintype "passive"))
    )
    (net (code "39") (name "/DM6R") (class "Default")
      (node (ref "R39") (pin "2") (pinfunction "2_2") (pintype "passive"))
    )
    (net (code "40") (name "/DM7") (class "Default")
      (node (ref "R59") (pin "1") (pinfunction "1_1") (pintype "passive"))
    )
    (net (code "41") (name "/DM7R") (class "Default")
      (node (ref "R59") (pin "2") (pinfunction "2_2") (pintype "passive"))
    )
    (net (code "42") (name "/DQ00") (class "Default")
      (node (ref "R32") (pin "1") (pinfunction "1_1") (pintype "passive"))
    )
    (net (code "43") (name "/DQ00R") (class "Default")
      (node (ref "R32") (pin "2") (pinfunction "2_2") (pintype "passive"))
    )
    (net (code "44") (name "/DQ01") (class "Default")
      (node (ref "R8") (pin "1") (pinfunction "1_1") (pintype "passive"))
    )
    (net (code "45") (name "/DQ01R") (class "Default")
      (node (ref "R8") (pin "2") (pinfunction "2_2") (pintype "passive"))
    )
    (net (code "46") (name "/DQ02") (class "Default")
      (node (ref "R44") (pin "1") (pinfunction "1_1") (pintype "passive"))
    )
    (net (code "47") (name "/DQ02R") (class "Default")
      (node (ref "R44") (pin "2") (pinfunction "2_2") (pintype "passive"))
    )
    (net (code "48") (name "/DQ03") (class "Default")
      (node (ref "R24") (pin "1") (pinfunction "1_1") (pintype "passive"))
    )
    (net (code "49") (name "/DQ03R") (class "Default")
      (node (ref "R24") (pin "2") (pinfunction "2_2") (pintype "passive"))
    )
    (net (code "50") (name "/DQ04") (class "Default")
      (node (ref "R28") (pin "1") (pinfunction "1_1") (pintype "passive"))
    )
    (net (code "51") (name "/DQ04R") (class "Default")
      (node (ref "R28") (pin "2") (pinfunction "2_2") (pintype "passive"))
    )
    (net (code "52") (name "/DQ05") (class "Default")
      (node (ref "R4") (pin "1") (pinfunction "1_1") (pintype "passive"))
    )
    (net (code "53") (name "/DQ05R") (class "Default")
      (node (ref "R4") (pin "2") (pinfunction "2_2") (pintype "passive"))
    )
    (net (code "54") (name "/DQ06") (class "Default")
      (node (ref "R40") (pin "1") (pinfunction "1_1") (pintype "passive"))
    )
    (net (code "55") (name "/DQ06R") (class "Default")
      (node (ref "R40") (pin "2") (pinfunction "2_2") (pintype "passive"))
    )
    (net (code "56") (name "/DQ07") (class "Default")
      (node (ref "R20") (pin "1") (pinfunction "1_1") (pintype "passive"))
    )
    (net (code "57") (name "/DQ07R") (class "Default")
      (node (ref "R20") (pin "2") (pinfunction "2_2") (pintype "passive"))
    )
    (net (code "58") (name "/DQ08") (class "Default")
      (node (ref "R72") (pin "1") (pinfunction "1_1") (pintype "passive"))
    )
    (net (code "59") (name "/DQ08R") (class "Default")
      (node (ref "R72") (pin "2") (pinfunction "2_2") (pintype "passive"))
    )
    (net (code "60") (name "/DQ09") (class "Default")
      (node (ref "R52") (pin "1") (pinfunction "1_1") (pintype "passive"))
    )
    (net (code "61") (name "/DQ09R") (class "Default")
      (node (ref "R52") (pin "2") (pinfunction "2_2") (pintype "passive"))
    )
    (net (code "62") (name "/DQ10") (class "Default")
      (node (ref "R64") (pin "1") (pinfunction "1_1") (pintype "passive"))
    )
    (net (code "63") (name "/DQ10R") (class "Default")
      (node (ref "R64") (pin "2") (pinfunction "2_2") (pintype "passive"))
    )
    (net (code "64") (name "/DQ11") (class "Default")
      (node (ref "R90") (pin "1") (pinfunction "1_1") (pintype "passive"))
    )
    (net (code "65") (name "/DQ11R") (class "Default")
      (node (ref "R90") (pin "2") (pinfunction "2_2") (pintype "passive"))
    )
    (net (code "66") (name "/DQ12") (class "Default")
      (node (ref "R68") (pin "1") (pinfunction "1_1") (pintype "passive"))
    )
    (net (code "67") (name "/DQ12R") (class "Default")
      (node (ref "R68") (pin "2") (pinfunction "2_2") (pintype "passive"))
    )
    (net (code "68") (name "/DQ13") (class "Default")
      (node (ref "R48") (pin "1") (pinfunction "1_1") (pintype "passive"))
    )
    (net (code "69") (name "/DQ13R") (class "Default")
      (node (ref "R48") (pin "2") (pinfunction "2_2") (pintype "passive"))
    )
    (net (code "70") (name "/DQ14") (class "Default")
      (node (ref "R86") (pin "1") (pinfunction "1_1") (pintype "passive"))
    )
    (net (code "71") (name "/DQ14R") (class "Default")
      (node (ref "R86") (pin "2") (pinfunction "2_2") (pintype "passive"))
    )
    (net (code "72") (name "/DQ15") (class "Default")
      (node (ref "R60") (pin "1") (pinfunction "1_1") (pintype "passive"))
    )
    (net (code "73") (name "/DQ15R") (class "Default")
      (node (ref "R60") (pin "2") (pinfunction "2_2") (pintype "passive"))
    )
    (net (code "74") (name "/DQ16") (class "Default")
      (node (ref "R33") (pin "1") (pinfunction "1_1") (pintype "passive"))
    )
    (net (code "75") (name "/DQ16R") (class "Default")
      (node (ref "R33") (pin "2") (pinfunction "2_2") (pintype "passive"))
    )
    (net (code "76") (name "/DQ17") (class "Default")
      (node (ref "R9") (pin "1") (pinfunction "1_1") (pintype "passive"))
    )
    (net (code "77") (name "/DQ17R") (class "Default")
      (node (ref "R9") (pin "2") (pinfunction "2_2") (pintype "passive"))
    )
    (net (code "78") (name "/DQ18") (class "Default")
      (node (ref "R45") (pin "1") (pinfunction "1_1") (pintype "passive"))
    )
    (net (code "79") (name "/DQ18R") (class "Default")
      (node (ref "R45") (pin "2") (pinfunction "2_2") (pintype "passive"))
    )
    (net (code "80") (name "/DQ19") (class "Default")
      (node (ref "R25") (pin "1") (pinfunction "1_1") (pintype "passive"))
    )
    (net (code "81") (name "/DQ19R") (class "Default")
      (node (ref "R25") (pin "2") (pinfunction "2_2") (pintype "passive"))
    )
    (net (code "82") (name "/DQ20") (class "Default")
      (node (ref "R29") (pin "1") (pinfunction "1_1") (pintype "passive"))
    )
    (net (code "83") (name "/DQ20R") (class "Default")
      (node (ref "R29") (pin "2") (pinfunction "2_2") (pintype "passive"))
    )
    (net (code "84") (name "/DQ21") (class "Default")
      (node (ref "R5") (pin "1") (pinfunction "1_1") (pintype "passive"))
    )
    (net (code "85") (name "/DQ21R") (class "Default")
      (node (ref "R5") (pin "2") (pinfunction "2_2") (pintype "passive"))
    )
    (net (code "86") (name "/DQ22") (class "Default")
      (node (ref "R41") (pin "1") (pinfunction "1_1") (pintype "passive"))
    )
    (net (code "87") (name "/DQ22R") (class "Default")
      (node (ref "R41") (pin "2") (pinfunction "2_2") (pintype "passive"))
    )
    (net (code "88") (name "/DQ23") (class "Default")
      (node (ref "R21") (pin "1") (pinfunction "1_1") (pintype "passive"))
    )
    (net (code "89") (name "/DQ23R") (class "Default")
      (node (ref "R21") (pin "2") (pinfunction "2_2") (pintype "passive"))
    )
    (net (code "90") (name "/DQ24") (class "Default")
      (node (ref "R73") (pin "1") (pinfunction "1_1") (pintype "passive"))
    )
    (net (code "91") (name "/DQ24R") (class "Default")
      (node (ref "R73") (pin "2") (pinfunction "2_2") (pintype "passive"))
    )
    (net (code "92") (name "/DQ25") (class "Default")
      (node (ref "R53") (pin "1") (pinfunction "1_1") (pintype "passive"))
    )
    (net (code "93") (name "/DQ25R") (class "Default")
      (node (ref "R53") (pin "2") (pinfunction "2_2") (pintype "passive"))
    )
    (net (code "94") (name "/DQ26") (class "Default")
      (node (ref "R65") (pin "1") (pinfunction "1_1") (pintype "passive"))
    )
    (net (code "95") (name "/DQ26R") (class "Default")
      (node (ref "R65") (pin "2") (pinfunction "2_2") (pintype "passive"))
    )
    (net (code "96") (name "/DQ27") (class "Default")
      (node (ref "R91") (pin "1") (pinfunction "1_1") (pintype "passive"))
    )
    (net (code "97") (name "/DQ27R") (class "Default")
      (node (ref "R91") (pin "2") (pinfunction "2_2") (pintype "passive"))
    )
    (net (code "98") (name "/DQ28") (class "Default")
      (node (ref "R69") (pin "1") (pinfunction "1_1") (pintype "passive"))
    )
    (net (code "99") (name "/DQ28R") (class "Default")
      (node (ref "R69") (pin "2") (pinfunction "2_2") (pintype "passive"))
    )
    (net (code "100") (name "/DQ29") (class "Default")
      (node (ref "R49") (pin "1") (pinfunction "1_1") (pintype "passive"))
    )
    (net (code "101") (name "/DQ29R") (class "Default")
      (node (ref "R49") (pin "2") (pinfunction "2_2") (pintype "passive"))
    )
    (net (code "102") (name "/DQ30") (class "Default")
      (node (ref "R61") (pin "1") (pinfunction "1_1") (pintype "passive"))
    )
    (net (code "103") (name "/DQ30R") (class "Default")
      (node (ref "R61") (pin "2") (pinfunction "2_2") (pintype "passive"))
    )
    (net (code "104") (name "/DQ31") (class "Default")
      (node (ref "R87") (pin "1") (pinfunction "1_1") (pintype "passive"))
    )
    (net (code "105") (name "/DQ31R") (class "Default")
      (node (ref "R87") (pin "2") (pinfunction "2_2") (pintype "passive"))
    )
    (net (code "106") (name "/DQ32") (class "Default")
      (node (ref "R34") (pin "1") (pinfunction "1_1") (pintype "passive"))
    )
    (net (code "107") (name "/DQ32R") (class "Default")
      (node (ref "R34") (pin "2") (pinfunction "2_2") (pintype "passive"))
    )
    (net (code "108") (name "/DQ33") (class "Default")
      (node (ref "R10") (pin "1") (pinfunction "1_1") (pintype "passive"))
    )
    (net (code "109") (name "/DQ33R") (class "Default")
      (node (ref "R10") (pin "2") (pinfunction "2_2") (pintype "passive"))
    )
    (net (code "110") (name "/DQ34") (class "Default")
      (node (ref "R26") (pin "1") (pinfunction "1_1") (pintype "passive"))
    )
    (net (code "111") (name "/DQ34R") (class "Default")
      (node (ref "R26") (pin "2") (pinfunction "2_2") (pintype "passive"))
    )
    (net (code "112") (name "/DQ35") (class "Default")
      (node (ref "R46") (pin "1") (pinfunction "1_1") (pintype "passive"))
    )
    (net (code "113") (name "/DQ35R") (class "Default")
      (node (ref "R46") (pin "2") (pinfunction "2_2") (pintype "passive"))
    )
    (net (code "114") (name "/DQ36") (class "Default")
      (node (ref "R30") (pin "1") (pinfunction "1_1") (pintype "passive"))
    )
    (net (code "115") (name "/DQ36R") (class "Default")
      (node (ref "R30") (pin "2") (pinfunction "2_2") (pintype "passive"))
    )
    (net (code "116") (name "/DQ37") (class "Default")
      (node (ref "R6") (pin "1") (pinfunction "1_1") (pintype "passive"))
    )
    (net (code "117") (name "/DQ37R") (class "Default")
      (node (ref "R6") (pin "2") (pinfunction "2_2") (pintype "passive"))
    )
    (net (code "118") (name "/DQ38") (class "Default")
      (node (ref "R22") (pin "1") (pinfunction "1_1") (pintype "passive"))
    )
    (net (code "119") (name "/DQ38R") (class "Default")
      (node (ref "R22") (pin "2") (pinfunction "2_2") (pintype "passive"))
    )
    (net (code "120") (name "/DQ39") (class "Default")
      (node (ref "R42") (pin "1") (pinfunction "1_1") (pintype "passive"))
    )
    (net (code "121") (name "/DQ39R") (class "Default")
      (node (ref "R42") (pin "2") (pinfunction "2_2") (pintype "passive"))
    )
    (net (code "122") (name "/DQ40") (class "Default")
      (node (ref "R54") (pin "1") (pinfunction "1_1") (pintype "passive"))
    )
    (net (code "123") (name "/DQ40R") (class "Default")
      (node (ref "R54") (pin "2") (pinfunction "2_2") (pintype "passive"))
    )
    (net (code "124") (name "/DQ41") (class "Default")
      (node (ref "R74") (pin "1") (pinfunction "1_1") (pintype "passive"))
    )
    (net (code "125") (name "/DQ41R") (class "Default")
      (node (ref "R74") (pin "2") (pinfunction "2_2") (pintype "passive"))
    )
    (net (code "126") (name "/DQ42") (class "Default")
      (node (ref "R66") (pin "1") (pinfunction "1_1") (pintype "passive"))
    )
    (net (code "127") (name "/DQ42R") (class "Default")
      (node (ref "R66") (pin "2") (pinfunction "2_2") (pintype "passive"))
    )
    (net (code "128") (name "/DQ43") (class "Default")
      (node (ref "R92") (pin "1") (pinfunction "1_1") (pintype "passive"))
    )
    (net (code "129") (name "/DQ43R") (class "Default")
      (node (ref "R92") (pin "2") (pinfunction "2_2") (pintype "passive"))
    )
    (net (code "130") (name "/DQ44") (class "Default")
      (node (ref "R50") (pin "1") (pinfunction "1_1") (pintype "passive"))
    )
    (net (code "131") (name "/DQ44R") (class "Default")
      (node (ref "R50") (pin "2") (pinfunction "2_2") (pintype "passive"))
    )
    (net (code "132") (name "/DQ45") (class "Default")
      (node (ref "R70") (pin "1") (pinfunction "1_1") (pintype "passive"))
    )
    (net (code "133") (name "/DQ45R") (class "Default")
      (node (ref "R70") (pin "2") (pinfunction "2_2") (pintype "passive"))
    )
    (net (code "134") (name "/DQ46") (class "Default")
      (node (ref "R62") (pin "1") (pinfunction "1_1") (pintype "passive"))
    )
    (net (code "135") (name "/DQ46R") (class "Default")
      (node (ref "R62") (pin "2") (pinfunction "2_2") (pintype "passive"))
    )
    (net (code "136") (name "/DQ47") (class "Default")
      (node (ref "R88") (pin "1") (pinfunction "1_1") (pintype "passive"))
    )
    (net (code "137") (name "/DQ47R") (class "Default")
      (node (ref "R88") (pin "2") (pinfunction "2_2") (pintype "passive"))
    )
    (net (code "138") (name "/DQ48") (class "Default")
      (node (ref "R35") (pin "1") (pinfunction "1_1") (pintype "passive"))
    )
    (net (code "139") (name "/DQ48R") (class "Default")
      (node (ref "R35") (pin "2") (pinfunction "2_2") (pintype "passive"))
    )
    (net (code "140") (name "/DQ49") (class "Default")
      (node (ref "R11") (pin "1") (pinfunction "1_1") (pintype "passive"))
    )
    (net (code "141") (name "/DQ49R") (class "Default")
      (node (ref "R11") (pin "2") (pinfunction "2_2") (pintype "passive"))
    )
    (net (code "142") (name "/DQ50") (class "Default")
      (node (ref "R47") (pin "1") (pinfunction "1_1") (pintype "passive"))
    )
    (net (code "143") (name "/DQ50R") (class "Default")
      (node (ref "R47") (pin "2") (pinfunction "2_2") (pintype "passive"))
    )
    (net (code "144") (name "/DQ51") (class "Default")
      (node (ref "R27") (pin "1") (pinfunction "1_1") (pintype "passive"))
    )
    (net (code "145") (name "/DQ51R") (class "Default")
      (node (ref "R27") (pin "2") (pinfunction "2_2") (pintype "passive"))
    )
    (net (code "146") (name "/DQ52") (class "Default")
      (node (ref "R7") (pin "1") (pinfunction "1_1") (pintype "passive"))
    )
    (net (code "147") (name "/DQ52R") (class "Default")
      (node (ref "R7") (pin "2") (pinfunction "2_2") (pintype "passive"))
    )
    (net (code "148") (name "/DQ53") (class "Default")
      (node (ref "R31") (pin "1") (pinfunction "1_1") (pintype "passive"))
    )
    (net (code "149") (name "/DQ53R") (class "Default")
      (node (ref "R31") (pin "2") (pinfunction "2_2") (pintype "passive"))
    )
    (net (code "150") (name "/DQ54") (class "Default")
      (node (ref "R43") (pin "1") (pinfunction "1_1") (pintype "passive"))
    )
    (net (code "151") (name "/DQ54R") (class "Default")
      (node (ref "R43") (pin "2") (pinfunction "2_2") (pintype "passive"))
    )
    (net (code "152") (name "/DQ55") (class "Default")
      (node (ref "R23") (pin "1") (pinfunction "1_1") (pintype "passive"))
    )
    (net (code "153") (name "/DQ55R") (class "Default")
      (node (ref "R23") (pin "2") (pinfunction "2_2") (pintype "passive"))
    )
    (net (code "154") (name "/DQ56") (class "Default")
      (node (ref "R55") (pin "1") (pinfunction "1_1") (pintype "passive"))
    )
    (net (code "155") (name "/DQ56R") (class "Default")
      (node (ref "R55") (pin "2") (pinfunction "2_2") (pintype "passive"))
    )
    (net (code "156") (name "/DQ57") (class "Default")
      (node (ref "R75") (pin "1") (pinfunction "1_1") (pintype "passive"))
    )
    (net (code "157") (name "/DQ57R") (class "Default")
      (node (ref "R75") (pin "2") (pinfunction "2_2") (pintype "passive"))
    )
    (net (code "158") (name "/DQ58") (class "Default")
      (node (ref "R67") (pin "1") (pinfunction "1_1") (pintype "passive"))
    )
    (net (code "159") (name "/DQ58R") (class "Default")
      (node (ref "R67") (pin "2") (pinfunction "2_2") (pintype "passive"))
    )
    (net (code "160") (name "/DQ59") (class "Default")
      (node (ref "R93") (pin "1") (pinfunction "1_1") (pintype "passive"))
    )
    (net (code "161") (name "/DQ59R") (class "Default")
      (node (ref "R93") (pin "2") (pinfunction "2_2") (pintype "passive"))
    )
    (net (code "162") (name "/DQ60") (class "Default")
      (node (ref "R71") (pin "1") (pinfunction "1_1") (pintype "passive"))
    )
    (net (code "163") (name "/DQ60R") (class "Default")
      (node (ref "R71") (pin "2") (pinfunction "2_2") (pintype "passive"))
    )
    (net (code "164") (name "/DQ61") (class "Default")
      (node (ref "R51") (pin "1") (pinfunction "1_1") (pintype "passive"))
    )
    (net (code "165") (name "/DQ61R") (class "Default")
      (node (ref "R51") (pin "2") (pinfunction "2_2") (pintype "passive"))
    )
    (net (code "166") (name "/DQ62") (class "Default")
      (node (ref "R63") (pin "1") (pinfunction "1_1") (pintype "passive"))
    )
    (net (code "167") (name "/DQ62R") (class "Default")
      (node (ref "R63") (pin "2") (pinfunction "2_2") (pintype "passive"))
    )
    (net (code "168") (name "/DQ63") (class "Default")
      (node (ref "R89") (pin "1") (pinfunction "1_1") (pintype "passive"))
    )
    (net (code "169") (name "/DQ63R") (class "Default")
      (node (ref "R89") (pin "2") (pinfunction "2_2") (pintype "passive"))
    )
    (net (code "170") (name "/DQS0R_N") (class "Default")
      (node (ref "R12") (pin "2") (pinfunction "2_2") (pintype "passive"))
    )
    (net (code "171") (name "/DQS0R_P") (class "Default")
      (node (ref "R16") (pin "2") (pinfunction "2_2") (pintype "passive"))
    )
    (net (code "172") (name "/DQS0_N") (class "Default")
      (node (ref "R12") (pin "1") (pinfunction "1_1") (pintype "passive"))
    )
    (net (code "173") (name "/DQS0_P") (class "Default")
      (node (ref "R16") (pin "1") (pinfunction "1_1") (pintype "passive"))
    )
    (net (code "174") (name "/DQS1R_N") (class "Default")
      (node (ref "R76") (pin "2") (pinfunction "2_2") (pintype "passive"))
    )
    (net (code "175") (name "/DQS1R_P") (class "Default")
      (node (ref "R81") (pin "2") (pinfunction "2_2") (pintype "passive"))
    )
    (net (code "176") (name "/DQS1_N") (class "Default")
      (node (ref "R76") (pin "1") (pinfunction "1_1") (pintype "passive"))
    )
    (net (code "177") (name "/DQS1_P") (class "Default")
      (node (ref "R81") (pin "1") (pinfunction "1_1") (pintype "passive"))
    )
    (net (code "178") (name "/DQS2R_N") (class "Default")
      (node (ref "R13") (pin "2") (pinfunction "2_2") (pintype "passive"))
    )
    (net (code "179") (name "/DQS2R_P") (class "Default")
      (node (ref "R17") (pin "2") (pinfunction "2_2") (pintype "passive"))
    )
    (net (code "180") (name "/DQS2_N") (class "Default")
      (node (ref "R13") (pin "1") (pinfunction "1_1") (pintype "passive"))
    )
    (net (code "181") (name "/DQS2_P") (class "Default")
      (node (ref "R17") (pin "1") (pinfunction "1_1") (pintype "passive"))
    )
    (net (code "182") (name "/DQS3R_N") (class "Default")
      (node (ref "R77") (pin "2") (pinfunction "2_2") (pintype "passive"))
    )
    (net (code "183") (name "/DQS3R_P") (class "Default")
      (node (ref "R82") (pin "2") (pinfunction "2_2") (pintype "passive"))
    )
    (net (code "184") (name "/DQS3_N") (class "Default")
      (node (ref "R77") (pin "1") (pinfunction "1_1") (pintype "passive"))
    )
    (net (code "185") (name "/DQS3_P") (class "Default")
      (node (ref "R82") (pin "1") (pinfunction "1_1") (pintype "passive"))
    )
    (net (code "186") (name "/DQS4R_N") (class "Default")
      (node (ref "R14") (pin "2") (pinfunction "2_2") (pintype "passive"))
    )
    (net (code "187") (name "/DQS4R_P") (class "Default")
      (node (ref "R18") (pin "2") (pinfunction "2_2") (pintype "passive"))
    )
    (net (code "188") (name "/DQS4_N") (class "Default")
      (node (ref "R14") (pin "1") (pinfunction "1_1") (pintype "passive"))
    )
    (net (code "189") (name "/DQS4_P") (class "Default")
      (node (ref "R18") (pin "1") (pinfunction "1_1") (pintype "passive"))
    )
    (net (code "190") (name "/DQS5R_N") (class "Default")
      (node (ref "R78") (pin "2") (pinfunction "2_2") (pintype "passive"))
    )
    (net (code "191") (name "/DQS5R_P") (class "Default")
      (node (ref "R83") (pin "2") (pinfunction "2_2") (pintype "passive"))
    )
    (net (code "192") (name "/DQS5_N") (class "Default")
      (node (ref "R78") (pin "1") (pinfunction "1_1") (pintype "passive"))
    )
    (net (code "193") (name "/DQS5_P") (class "Default")
      (node (ref "R83") (pin "1") (pinfunction "1_1") (pintype "passive"))
    )
    (net (code "194") (name "/DQS6R_N") (class "Default")
      (node (ref "R15") (pin "2") (pinfunction "2_2") (pintype "passive"))
    )
    (net (code "195") (name "/DQS6R_P") (class "Default")
      (node (ref "R19") (pin "2") (pinfunction "2_2") (pintype "passive"))
    )
    (net (code "196") (name "/DQS6_N") (class "Default")
      (node (ref "R15") (pin "1") (pinfunction "1_1") (pintype "passive"))
    )
    (net (code "197") (name "/DQS6_P") (class "Default")
      (node (ref "R19") (pin "1") (pinfunction "1_1") (pintype "passive"))
    )
    (net (code "198") (name "/DQS7R_N") (class "Default")
      (node (ref "R79") (pin "2") (pinfunction "2_2") (pintype "passive"))
    )
    (net (code "199") (name "/DQS7R_P") (class "Default")
      (node (ref "R84") (pin "2") (pinfunction "2_2") (pintype "passive"))
    )
    (net (code "200") (name "/DQS7_N") (class "Default")
      (node (ref "R79") (pin "1") (pinfunction "1_1") (pintype "passive"))
    )
    (net (code "201") (name "/DQS7_P") (class "Default")
      (node (ref "R84") (pin "1") (pinfunction "1_1") (pintype "passive"))
    )
    (net (code "202") (name "/ODT0") (class "Default")
      (node (ref "RN1") (pin "2") (pinfunction "2_2") (pintype "passive"))
    )
    (net (code "203") (name "/PARITY") (class "Default")
      (node (ref "RN6") (pin "2") (pinfunction "2_2") (pintype "passive"))
    )
    (net (code "204") (name "/S0") (class "Default")
      (node (ref "RN1") (pin "1") (pinfunction "1_1") (pintype "passive"))
    )
    (net (code "205") (name "/VDD") (class "Default")
      (node (ref "C4") (pin "2") (pinfunction "2_2") (pintype "passive"))
    )
    (net (code "206") (name "/VTT") (class "Default")
      (node (ref "RN1") (pin "5") (pinfunction "5_5") (pintype "passive"))
      (node (ref "RN1") (pin "6") (pinfunction "6_6") (pintype "passive"))
      (node (ref "RN1") (pin "7") (pinfunction "7_7") (pintype "passive"))
      (node (ref "RN1") (pin "8") (pinfunction "8_8") (pintype "passive"))
      (node (ref "RN2") (pin "5") (pinfunction "5_5") (pintype "passive"))
      (node (ref "RN2") (pin "6") (pinfunction "6_6") (pintype "passive"))
      (node (ref "RN2") (pin "7") (pinfunction "7_7") (pintype "passive"))
      (node (ref "RN2") (pin "8") (pinfunction "8_8") (pintype "passive"))
      (node (ref "RN3") (pin "5") (pinfunction "5_5") (pintype "passive"))
      (node (ref "RN3") (pin "6") (pinfunction "6_6") (pintype "passive"))
      (node (ref "RN3") (pin "7") (pinfunction "7_7") (pintype "passive"))
      (node (ref "RN3") (pin "8") (pinfunction "8_8") (pintype "passive"))
      (node (ref "RN4") (pin "5") (pinfunction "5_5") (pintype "passive"))
      (node (ref "RN4") (pin "6") (pinfunction "6_6") (pintype "passive"))
      (node (ref "RN4") (pin "7") (pinfunction "7_7") (pintype "passive"))
      (node (ref "RN4") (pin "8") (pinfunction "8_8") (pintype "passive"))
      (node (ref "RN5") (pin "5") (pinfunction "5_5") (pintype "passive"))
      (node (ref "RN5") (pin "6") (pinfunction "6_6") (pintype "passive"))
      (node (ref "RN5") (pin "7") (pinfunction "7_7") (pintype "passive"))
      (node (ref "RN5") (pin "8") (pinfunction "8_8") (pintype "passive"))
      (node (ref "RN6") (pin "5") (pinfunction "5_5") (pintype "passive"))
      (node (ref "RN6") (pin "6") (pinfunction "6_6") (pintype "passive"))
      (node (ref "RN6") (pin "7") (pinfunction "7_7") (pintype "passive"))
      (node (ref "RN6") (pin "8") (pinfunction "8_8") (pintype "passive"))
      (node (ref "RN7") (pin "5") (pinfunction "5_5") (pintype "passive"))
      (node (ref "RN7") (pin "6") (pinfunction "6_6") (pintype "passive"))
      (node (ref "RN7") (pin "7") (pinfunction "7_7") (pintype "passive"))
      (node (ref "RN7") (pin "8") (pinfunction "8_8") (pintype "passive"))
    )
    (net (code "208") (name "Net-(C4-Pad1)") (class "Default")
      (node (ref "C4") (pin "1") (pinfunction "1_1") (pintype "passive"))
      (node (ref "R80") (pin "2") (pinfunction "2_2") (pintype "passive"))
      (node (ref "R85") (pin "2") (pinfunction "2_2") (pintype "passive"))
    )
    (net (code "209") (name "unconnected-(RN1-Pad3)") (class "Default")
      (node (ref "RN1") (pin "3") (pinfunction "3_3") (pintype "passive"))
    )
    (net (code "210") (name "unconnected-(RN4-Pad4)") (class "Default")
      (node (ref "RN4") (pin "4") (pinfunction "4_4") (pintype "passive"))
    )
  )
)
